# fuentesimetricafinal.net
KiCad netlist of a schematic drawn in EAGLE
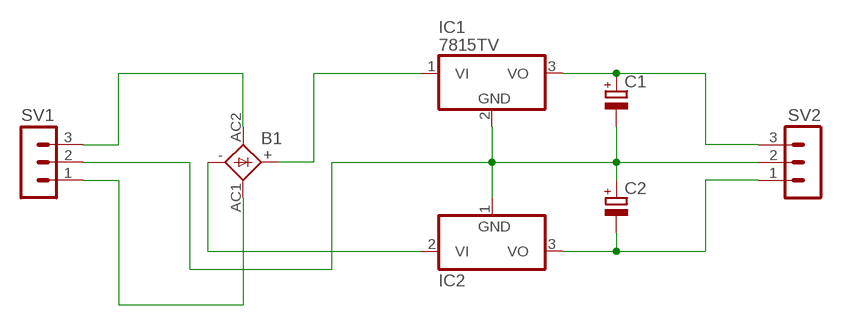
[diagram p0: schematic, sheet 1]

(export (version "E")
  (design (tool "Eeschema 10.0.6"))
  (components
    (comp (ref "B1")
      (value "FBU4")
      (footprint "eagle-import:FBU4")
      (libsource (lib "eagle-import") (part "FBU4"))
    )
    (comp (ref "C1")
      (value "CPOL-EUE3.5-8")
      (footprint "eagle-import:E3,5-8")
      (libsource (lib "eagle-import") (part "CPOL-EUE3.5-8"))
    )
    (comp (ref "C2")
      (value "CPOL-EUE3.5-8")
      (footprint "eagle-import:E3,5-8")
      (libsource (lib "eagle-import") (part "CPOL-EUE3.5-8"))
    )
    (comp (ref "IC1")
      (value "7815TV")
      (footprint "eagle-import:TO220V")
      (libsource (lib "eagle-import") (part "78TV15"))
    )
    (comp (ref "IC2")
      (value "7915T")
      (footprint "eagle-import:TO220H")
      (libsource (lib "eagle-import") (part "79T15"))
    )
    (comp (ref "SV1")
      (value "MA03-1")
      (footprint "eagle-import:MA03-1")
      (libsource (lib "eagle-import") (part "MA03-1"))
    )
    (comp (ref "SV2")
      (value "MA03-1")
      (footprint "eagle-import:MA03-1")
      (libsource (lib "eagle-import") (part "MA03-1"))
    )
  )
  (nets
    (net (code "1") (name "Net-(B1-AC1)") (class "Default")
      (node (ref "B1") (pin "AC2") (pinfunction "AC1_AC2") (pintype "passive"))
      (node (ref "SV1") (pin "3") (pinfunction "3_3") (pintype "passive"))
    )
    (net (code "2") (name "Net-(B1-AC2)") (class "Default")
      (node (ref "B1") (pin "AC1") (pinfunction "AC2_AC1") (pintype "passive"))
      (node (ref "SV1") (pin "1") (pinfunction "1_1") (pintype "passive"))
    )
    (net (code "3") (name "Net-(IC1-GND)") (class "Default")
      (node (ref "C1") (pin "-") (pinfunction "-_-") (pintype "passive"))
      (node (ref "C2") (pin "+") (pinfunction "+_+") (pintype "passive"))
      (node (ref "IC1") (pin "2") (pinfunction "GND_2") (pintype "passive"))
      (node (ref "IC2") (pin "1") (pinfunction "GND_1") (pintype "passive"))
      (node (ref "SV1") (pin "2") (pinfunction "2_2") (pintype "passive"))
      (node (ref "SV2") (pin "2") (pinfunction "2_2") (pintype "passive"))
    )
    (net (code "4") (name "Net-(IC1-VI)") (class "Default")
      (node (ref "B1") (pin "+") (pinfunction "+_+") (pintype "passive"))
      (node (ref "IC1") (pin "1") (pinfunction "VI_1") (pintype "input"))
    )
    (net (code "5") (name "Net-(IC1-VO)") (class "Default")
      (node (ref "C1") (pin "+") (pinfunction "+_+") (pintype "passive"))
      (node (ref "IC1") (pin "3") (pinfunction "VO_3") (pintype "passive"))
      (node (ref "SV2") (pin "3") (pinfunction "3_3") (pintype "passive"))
    )
    (net (code "6") (name "Net-(IC2-VI)") (class "Default")
      (node (ref "B1") (pin "-") (pinfunction "-_-") (pintype "passive"))
      (node (ref "IC2") (pin "2") (pinfunction "VI_2") (pintype "input"))
    )
    (net (code "7") (name "Net-(IC2-VO)") (class "Default")
      (node (ref "C2") (pin "-") (pinfunction "-_-") (pintype "passive"))
      (node (ref "IC2") (pin "3") (pinfunction "VO_3") (pintype "passive"))
      (node (ref "SV2") (pin "1") (pinfunction "1_1") (pintype "passive"))
    )
  )
)
